# MainBoard.net
KiCad netlist of a schematic drawn in EAGLE
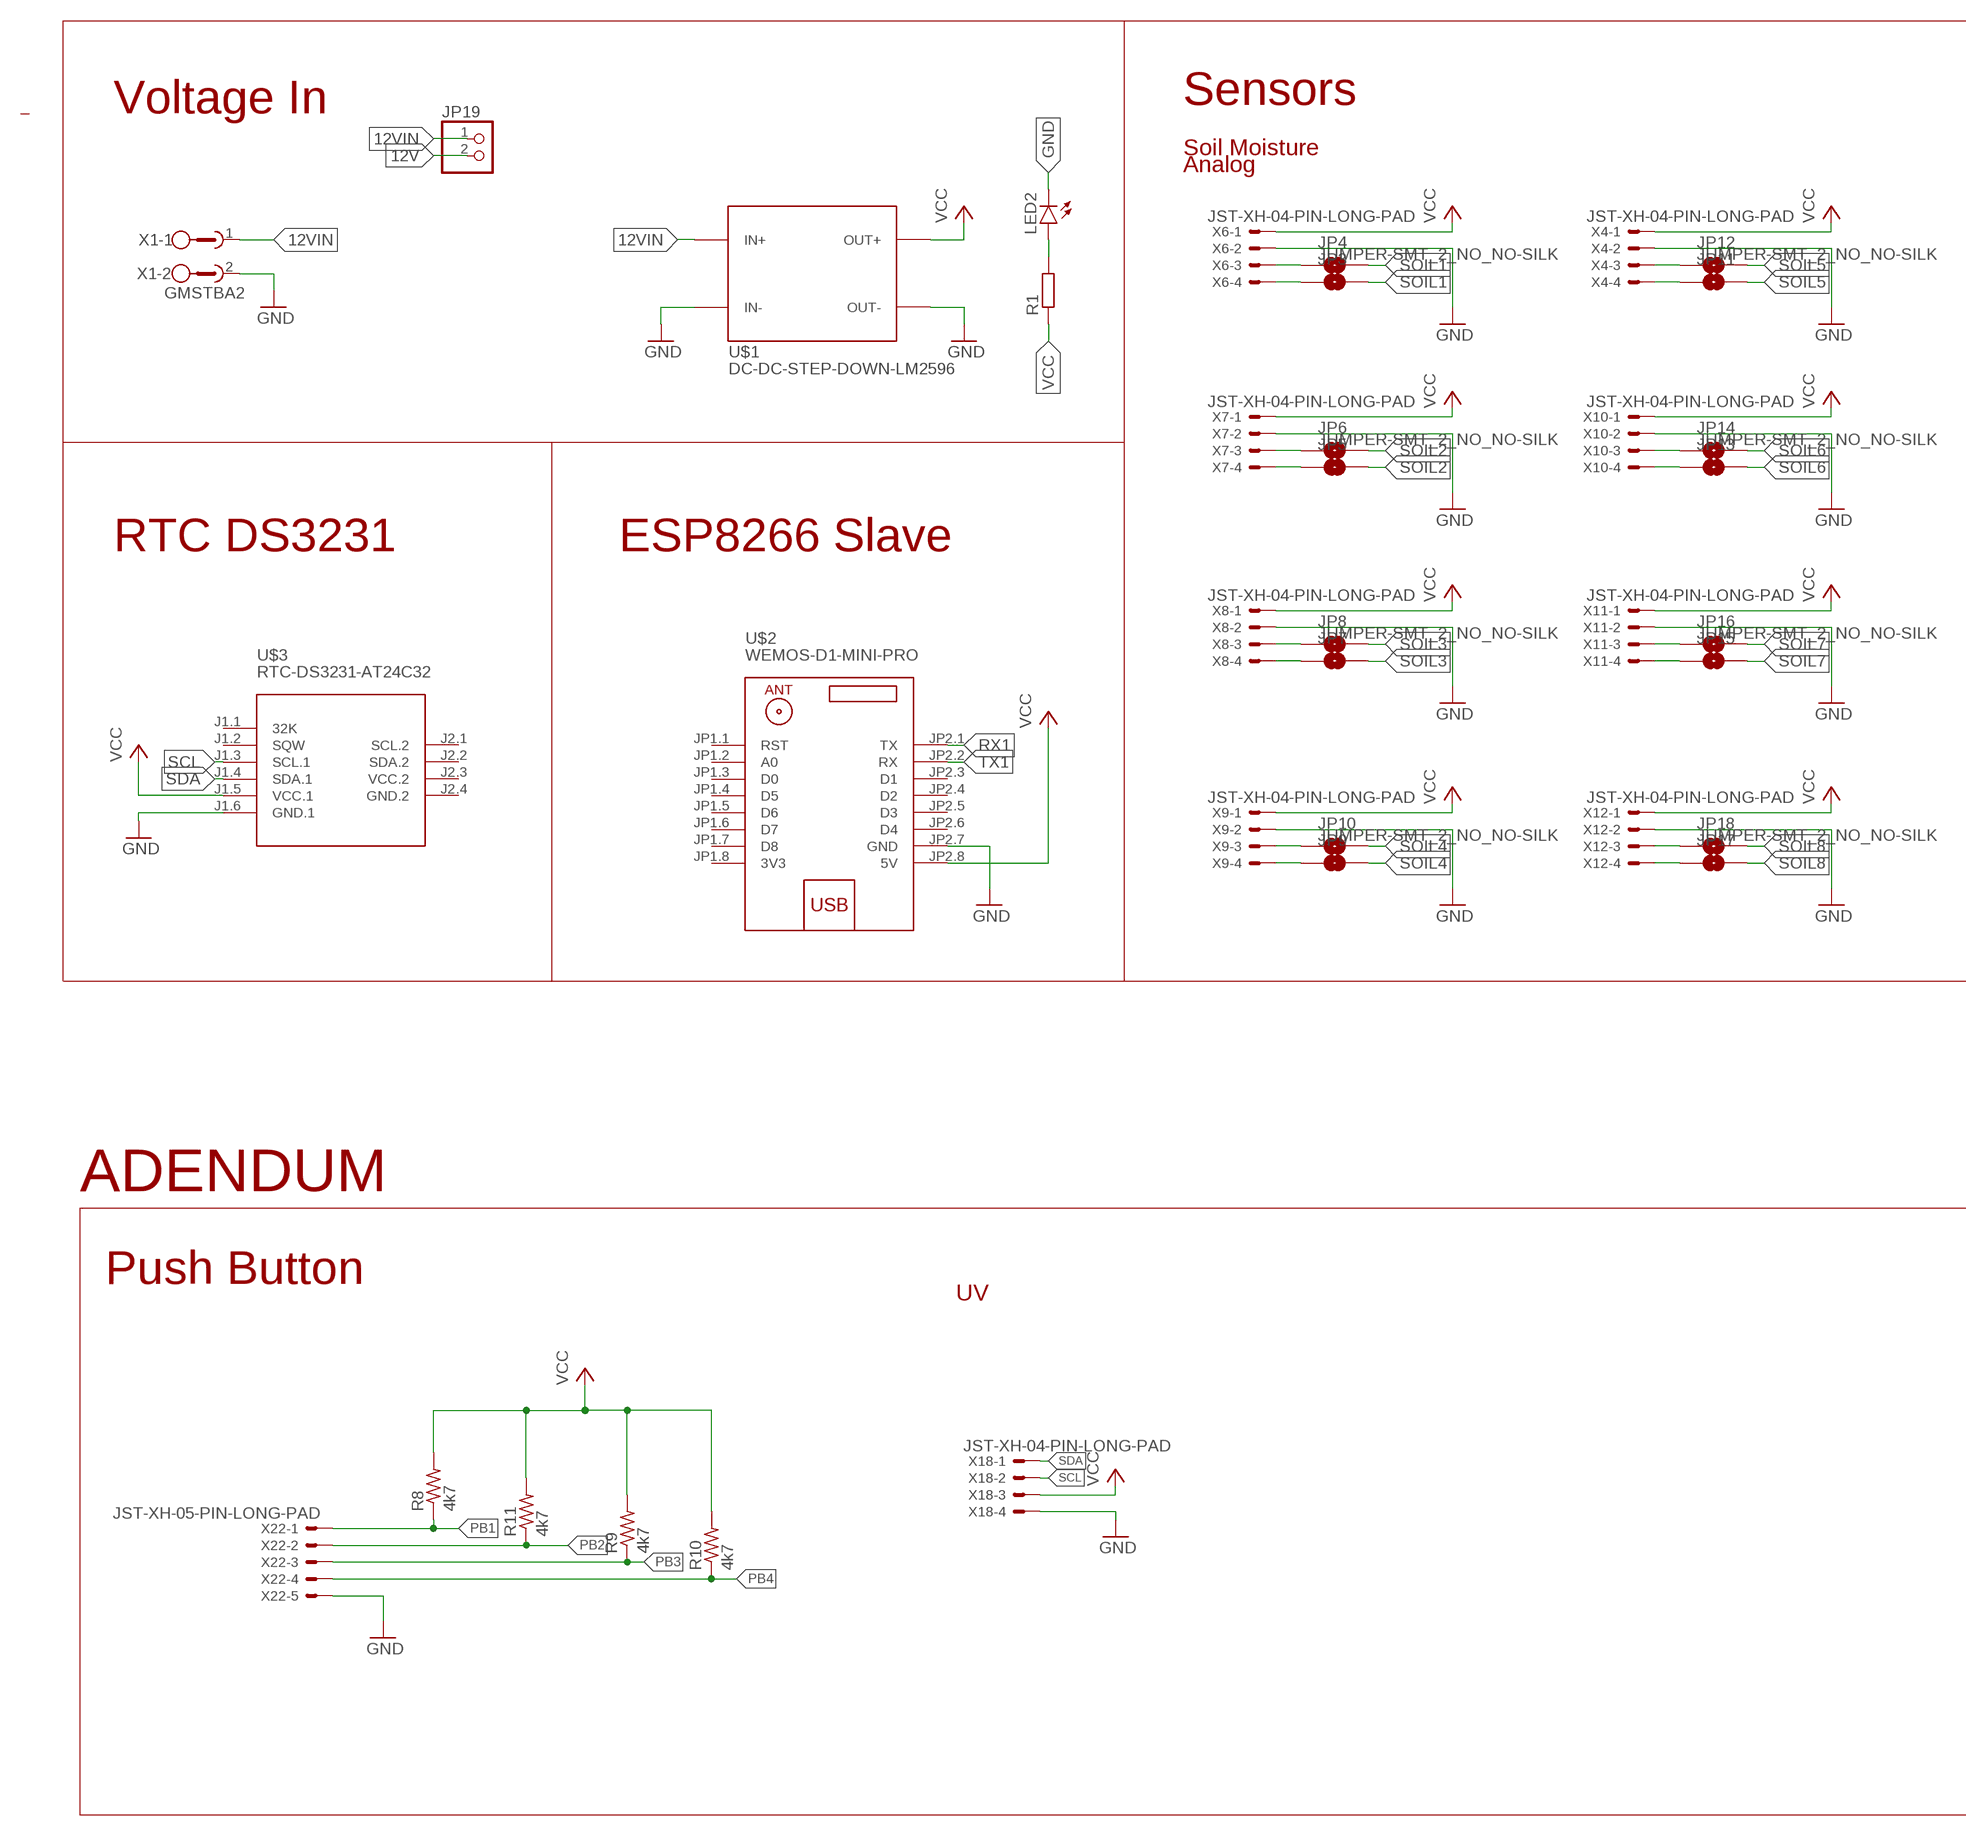
[diagram p0: schematic, sheet 1, part 1 of 2]
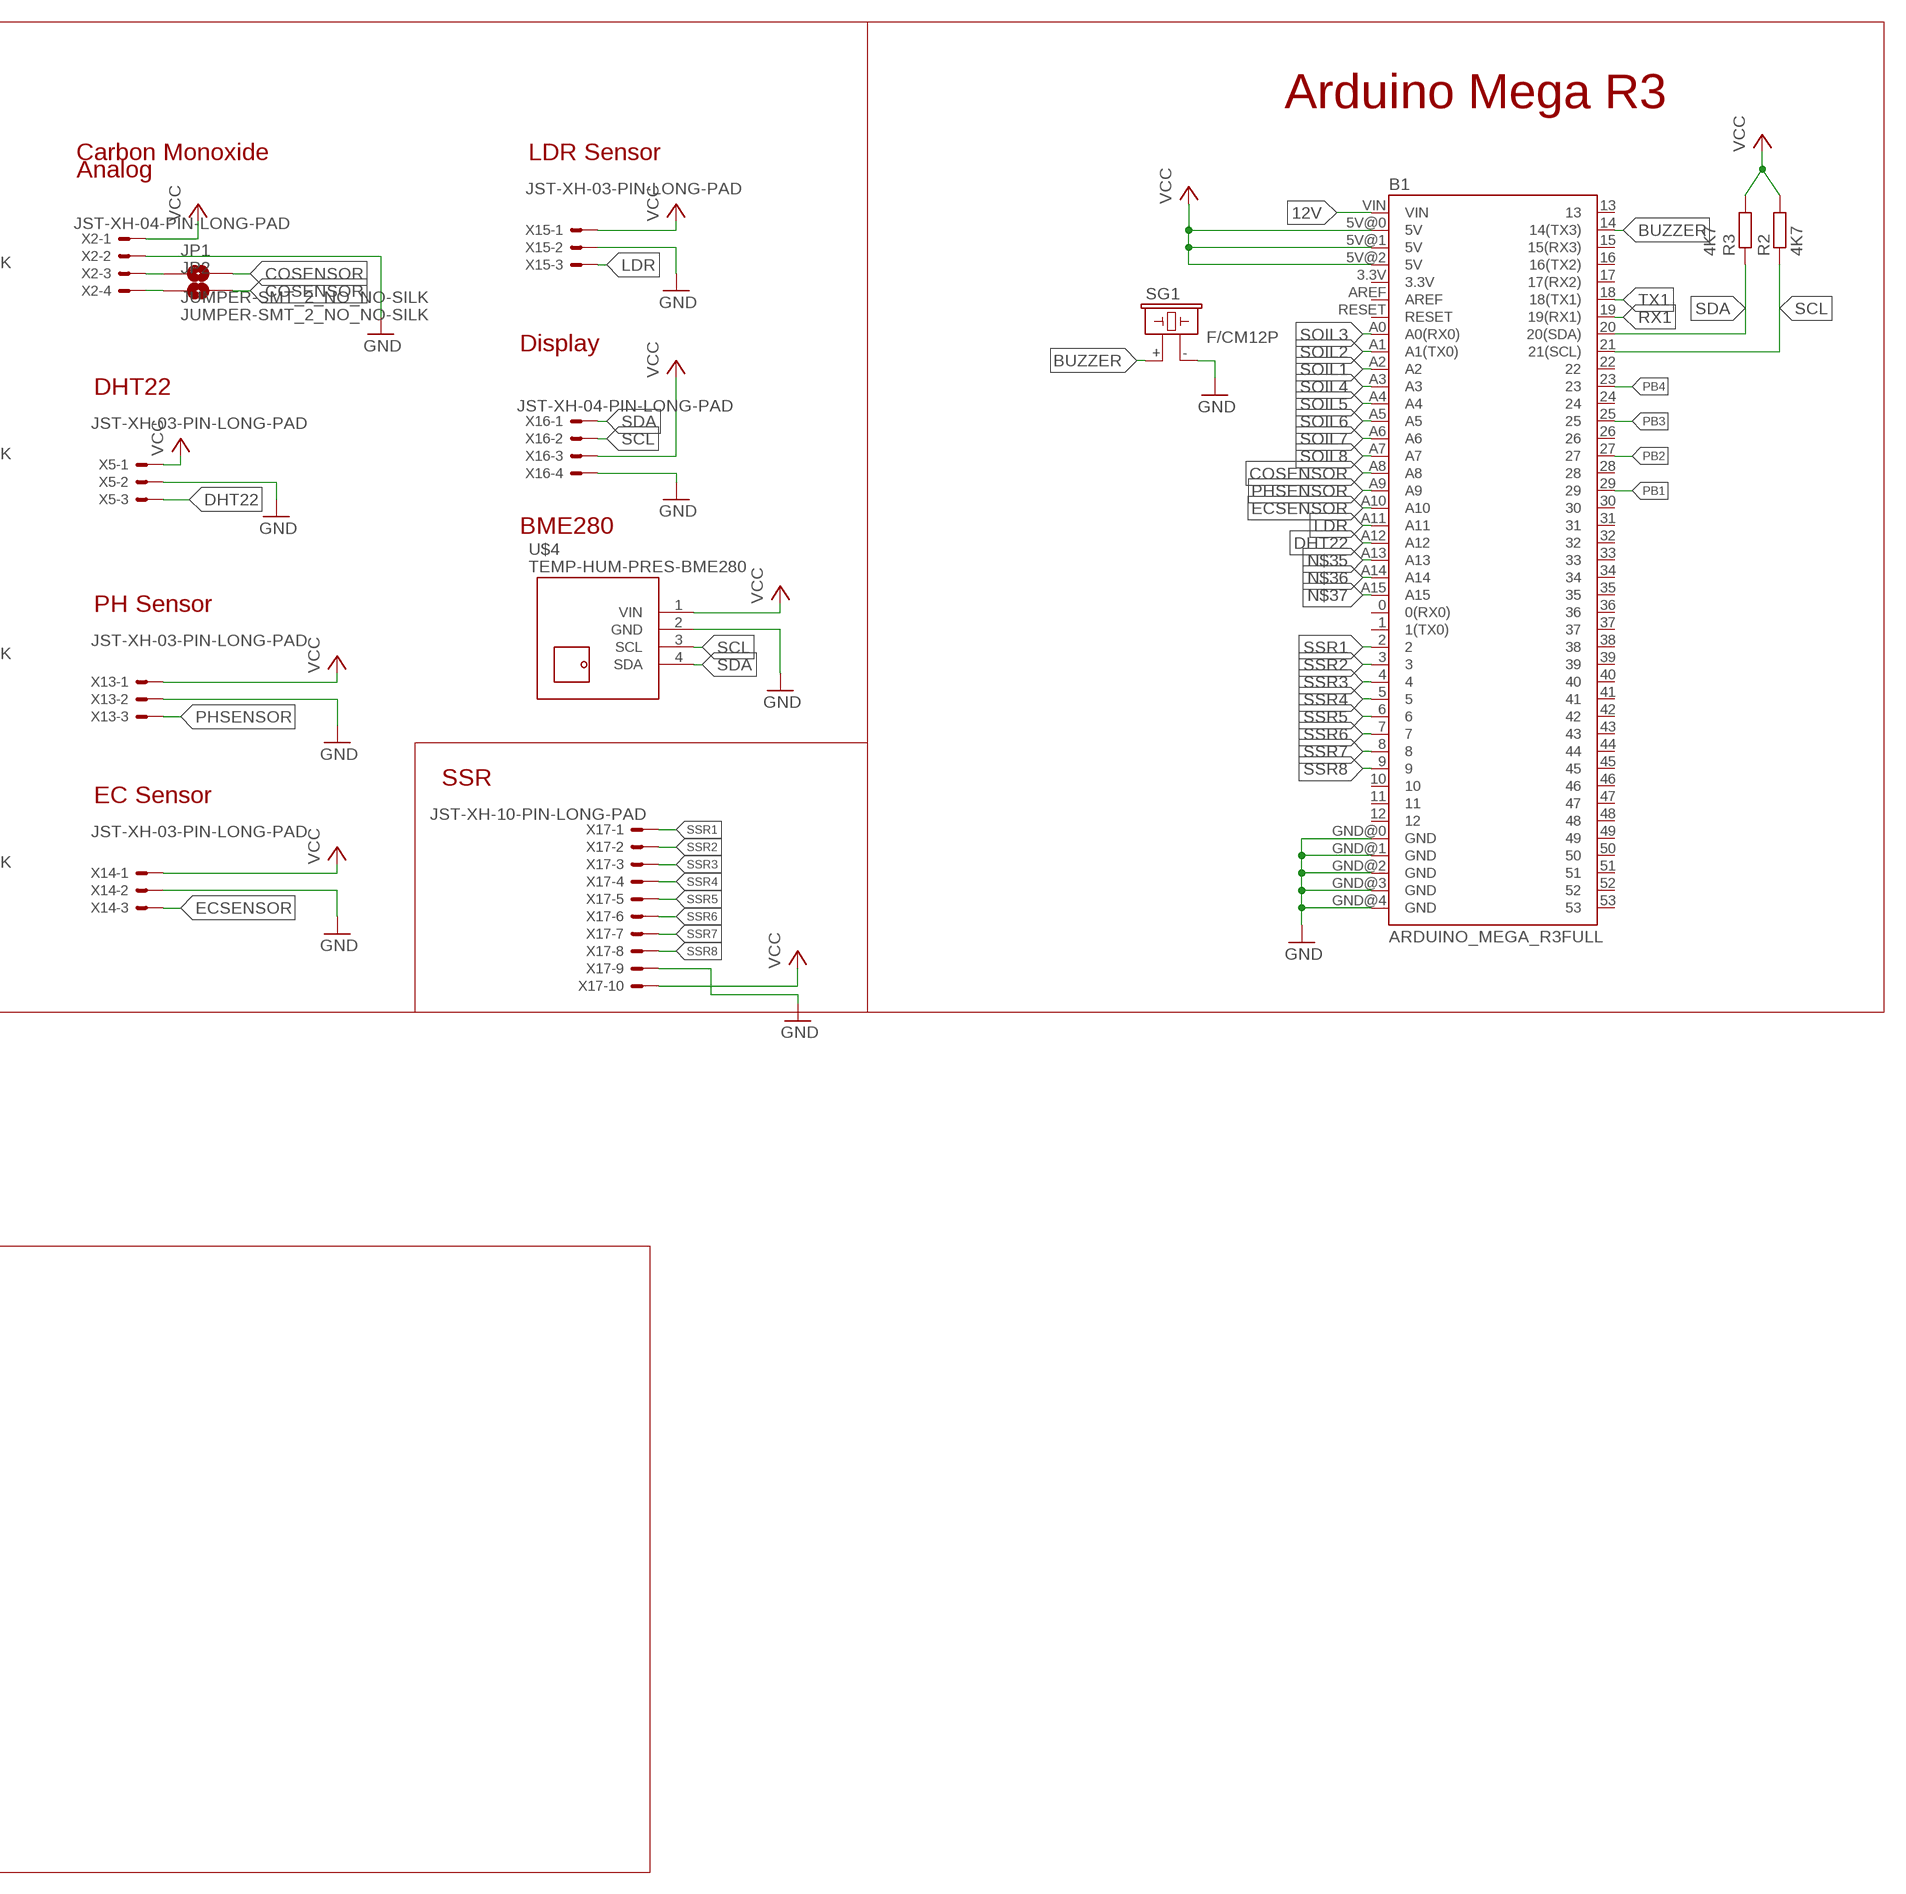
[diagram p1: schematic, sheet 1, part 2 of 2]

(export (version "E")
  (design (tool "Eeschema 10.0.6"))
  (components
    (comp (ref "B1")
      (value "ARDUINO_MEGA_R3FULL")
      (footprint "eagle-import:ARDUINO_MEGA")
      (libsource (lib "eagle-import") (part "ARDUINO_MEGA_R3FULL"))
    )
    (comp (ref "JP1")
      (value "JUMPER-SMT_2_NO_NO-SILK")
      (footprint "eagle-import:SMT-JUMPER_2_NO_NO-SILK")
      (libsource (lib "eagle-import") (part "JUMPER-SMT_2_NO_NO-SILK"))
    )
    (comp (ref "JP2")
      (value "JUMPER-SMT_2_NO_NO-SILK")
      (footprint "eagle-import:SMT-JUMPER_2_NO_NO-SILK")
      (libsource (lib "eagle-import") (part "JUMPER-SMT_2_NO_NO-SILK"))
    )
    (comp (ref "JP3")
      (value "JUMPER-SMT_2_NO_NO-SILK")
      (footprint "eagle-import:SMT-JUMPER_2_NO_NO-SILK")
      (libsource (lib "eagle-import") (part "JUMPER-SMT_2_NO_NO-SILK"))
    )
    (comp (ref "JP4")
      (value "JUMPER-SMT_2_NO_NO-SILK")
      (footprint "eagle-import:SMT-JUMPER_2_NO_NO-SILK")
      (libsource (lib "eagle-import") (part "JUMPER-SMT_2_NO_NO-SILK"))
    )
    (comp (ref "JP5")
      (value "JUMPER-SMT_2_NO_NO-SILK")
      (footprint "eagle-import:SMT-JUMPER_2_NO_NO-SILK")
      (libsource (lib "eagle-import") (part "JUMPER-SMT_2_NO_NO-SILK"))
    )
    (comp (ref "JP6")
      (value "JUMPER-SMT_2_NO_NO-SILK")
      (footprint "eagle-import:SMT-JUMPER_2_NO_NO-SILK")
      (libsource (lib "eagle-import") (part "JUMPER-SMT_2_NO_NO-SILK"))
    )
    (comp (ref "JP7")
      (value "JUMPER-SMT_2_NO_NO-SILK")
      (footprint "eagle-import:SMT-JUMPER_2_NO_NO-SILK")
      (libsource (lib "eagle-import") (part "JUMPER-SMT_2_NO_NO-SILK"))
    )
    (comp (ref "JP8")
      (value "JUMPER-SMT_2_NO_NO-SILK")
      (footprint "eagle-import:SMT-JUMPER_2_NO_NO-SILK")
      (libsource (lib "eagle-import") (part "JUMPER-SMT_2_NO_NO-SILK"))
    )
    (comp (ref "JP9")
      (value "JUMPER-SMT_2_NO_NO-SILK")
      (footprint "eagle-import:SMT-JUMPER_2_NO_NO-SILK")
      (libsource (lib "eagle-import") (part "JUMPER-SMT_2_NO_NO-SILK"))
    )
    (comp (ref "JP10")
      (value "JUMPER-SMT_2_NO_NO-SILK")
      (footprint "eagle-import:SMT-JUMPER_2_NO_NO-SILK")
      (libsource (lib "eagle-import") (part "JUMPER-SMT_2_NO_NO-SILK"))
    )
    (comp (ref "JP11")
      (value "JUMPER-SMT_2_NO_NO-SILK")
      (footprint "eagle-import:SMT-JUMPER_2_NO_NO-SILK")
      (libsource (lib "eagle-import") (part "JUMPER-SMT_2_NO_NO-SILK"))
    )
    (comp (ref "JP12")
      (value "JUMPER-SMT_2_NO_NO-SILK")
      (footprint "eagle-import:SMT-JUMPER_2_NO_NO-SILK")
      (libsource (lib "eagle-import") (part "JUMPER-SMT_2_NO_NO-SILK"))
    )
    (comp (ref "JP13")
      (value "JUMPER-SMT_2_NO_NO-SILK")
      (footprint "eagle-import:SMT-JUMPER_2_NO_NO-SILK")
      (libsource (lib "eagle-import") (part "JUMPER-SMT_2_NO_NO-SILK"))
    )
    (comp (ref "JP14")
      (value "JUMPER-SMT_2_NO_NO-SILK")
      (footprint "eagle-import:SMT-JUMPER_2_NO_NO-SILK")
      (libsource (lib "eagle-import") (part "JUMPER-SMT_2_NO_NO-SILK"))
    )
    (comp (ref "JP15")
      (value "JUMPER-SMT_2_NO_NO-SILK")
      (footprint "eagle-import:SMT-JUMPER_2_NO_NO-SILK")
      (libsource (lib "eagle-import") (part "JUMPER-SMT_2_NO_NO-SILK"))
    )
    (comp (ref "JP16")
      (value "JUMPER-SMT_2_NO_NO-SILK")
      (footprint "eagle-import:SMT-JUMPER_2_NO_NO-SILK")
      (libsource (lib "eagle-import") (part "JUMPER-SMT_2_NO_NO-SILK"))
    )
    (comp (ref "JP17")
      (value "JUMPER-SMT_2_NO_NO-SILK")
      (footprint "eagle-import:SMT-JUMPER_2_NO_NO-SILK")
      (libsource (lib "eagle-import") (part "JUMPER-SMT_2_NO_NO-SILK"))
    )
    (comp (ref "JP18")
      (value "JUMPER-SMT_2_NO_NO-SILK")
      (footprint "eagle-import:SMT-JUMPER_2_NO_NO-SILK")
      (libsource (lib "eagle-import") (part "JUMPER-SMT_2_NO_NO-SILK"))
    )
    (comp (ref "JP19")
      (value "PINHD-1X2")
      (footprint "eagle-import:1X02")
      (libsource (lib "eagle-import") (part "PINHD-1X2"))
    )
    (comp (ref "LED2")
      (value "LED5MM")
      (footprint "eagle-import:LED5MM")
      (libsource (lib "eagle-import") (part "LED5MM"))
    )
    (comp (ref "R1")
      (value "R-EU_R0805")
      (footprint "eagle-import:R0805")
      (libsource (lib "eagle-import") (part "rcl_334_R-EU_R0805"))
    )
    (comp (ref "R2")
      (value "4K7")
      (footprint "eagle-import:M0805")
      (libsource (lib "eagle-import") (part "R-EU_M0805"))
    )
    (comp (ref "R3")
      (value "4K7")
      (footprint "eagle-import:M0805")
      (libsource (lib "eagle-import") (part "R-EU_M0805"))
    )
    (comp (ref "R8")
      (value "4k7")
      (footprint "eagle-import:M0805")
      (libsource (lib "eagle-import") (part "R-US_M0805"))
    )
    (comp (ref "R9")
      (value "4k7")
      (footprint "eagle-import:M0805")
      (libsource (lib "eagle-import") (part "R-US_M0805"))
    )
    (comp (ref "R10")
      (value "4k7")
      (footprint "eagle-import:M0805")
      (libsource (lib "eagle-import") (part "R-US_M0805"))
    )
    (comp (ref "R11")
      (value "4k7")
      (footprint "eagle-import:M0805")
      (libsource (lib "eagle-import") (part "R-US_M0805"))
    )
    (comp (ref "SG1")
      (value "F/CM12P")
      (footprint "eagle-import:F_CM12P")
      (libsource (lib "eagle-import") (part "F/CM12P"))
    )
    (comp (ref "U$1")
      (value "DC-DC-STEP-DOWN-LM2596")
      (footprint "eagle-import:DC-DC-STEP-DOWN-LM2596")
      (libsource (lib "eagle-import") (part "DC-DC-STEP-DOWN-LM2596"))
    )
    (comp (ref "U$2")
      (value "WEMOS-D1-MINI-PRO")
      (footprint "eagle-import:WEMOS-D1-MINI-PRO")
      (libsource (lib "eagle-import") (part "WEMOS-D1-MINI-PRO"))
    )
    (comp (ref "U$3")
      (value "RTC-DS3231-AT24C32")
      (footprint "eagle-import:RTC-DS3231-AT24C32")
      (libsource (lib "eagle-import") (part "RTC-DS3231-AT24C32"))
    )
    (comp (ref "U$4")
      (value "TEMP-HUM-PRES-BME280")
      (footprint "eagle-import:TEMP-HUM-PRES-BME280")
      (libsource (lib "eagle-import") (part "TEMP-HUM-PRES-BME280"))
    )
    (comp (ref "X1")
      (value "GMSTBA2")
      (footprint "eagle-import:GMSTBA2")
      (fields (field (name "MF") "FARNELL") (field (name "MPN") "1757242"))
      (libsource (lib "eagle-import") (part "GMSTBA2"))
    )
    (comp (ref "X2")
      (value "JST-XH-04-PIN-LONG-PAD")
      (footprint "eagle-import:JST-XH-04-PACKAGE-LONG-PAD")
      (libsource (lib "eagle-import") (part "JST-XH-04-PIN-LONG-PAD"))
    )
    (comp (ref "X4")
      (value "JST-XH-04-PIN-LONG-PAD")
      (footprint "eagle-import:JST-XH-04-PACKAGE-LONG-PAD")
      (libsource (lib "eagle-import") (part "JST-XH-04-PIN-LONG-PAD"))
    )
    (comp (ref "X5")
      (value "JST-XH-03-PIN-LONG-PAD")
      (footprint "eagle-import:JST-XH-03-PACKAGE-LONG-PAD")
      (libsource (lib "eagle-import") (part "JST-XH-03-PIN-LONG-PAD"))
    )
    (comp (ref "X6")
      (value "JST-XH-04-PIN-LONG-PAD")
      (footprint "eagle-import:JST-XH-04-PACKAGE-LONG-PAD")
      (libsource (lib "eagle-import") (part "JST-XH-04-PIN-LONG-PAD"))
    )
    (comp (ref "X7")
      (value "JST-XH-04-PIN-LONG-PAD")
      (footprint "eagle-import:JST-XH-04-PACKAGE-LONG-PAD")
      (libsource (lib "eagle-import") (part "JST-XH-04-PIN-LONG-PAD"))
    )
    (comp (ref "X8")
      (value "JST-XH-04-PIN-LONG-PAD")
      (footprint "eagle-import:JST-XH-04-PACKAGE-LONG-PAD")
      (libsource (lib "eagle-import") (part "JST-XH-04-PIN-LONG-PAD"))
    )
    (comp (ref "X9")
      (value "JST-XH-04-PIN-LONG-PAD")
      (footprint "eagle-import:JST-XH-04-PACKAGE-LONG-PAD")
      (libsource (lib "eagle-import") (part "JST-XH-04-PIN-LONG-PAD"))
    )
    (comp (ref "X10")
      (value "JST-XH-04-PIN-LONG-PAD")
      (footprint "eagle-import:JST-XH-04-PACKAGE-LONG-PAD")
      (libsource (lib "eagle-import") (part "JST-XH-04-PIN-LONG-PAD"))
    )
    (comp (ref "X11")
      (value "JST-XH-04-PIN-LONG-PAD")
      (footprint "eagle-import:JST-XH-04-PACKAGE-LONG-PAD")
      (libsource (lib "eagle-import") (part "JST-XH-04-PIN-LONG-PAD"))
    )
    (comp (ref "X12")
      (value "JST-XH-04-PIN-LONG-PAD")
      (footprint "eagle-import:JST-XH-04-PACKAGE-LONG-PAD")
      (libsource (lib "eagle-import") (part "JST-XH-04-PIN-LONG-PAD"))
    )
    (comp (ref "X13")
      (value "JST-XH-03-PIN-LONG-PAD")
      (footprint "eagle-import:JST-XH-03-PACKAGE-LONG-PAD")
      (libsource (lib "eagle-import") (part "JST-XH-03-PIN-LONG-PAD"))
    )
    (comp (ref "X14")
      (value "JST-XH-03-PIN-LONG-PAD")
      (footprint "eagle-import:JST-XH-03-PACKAGE-LONG-PAD")
      (libsource (lib "eagle-import") (part "JST-XH-03-PIN-LONG-PAD"))
    )
    (comp (ref "X15")
      (value "JST-XH-03-PIN-LONG-PAD")
      (footprint "eagle-import:JST-XH-03-PACKAGE-LONG-PAD")
      (libsource (lib "eagle-import") (part "JST-XH-03-PIN-LONG-PAD"))
    )
    (comp (ref "X16")
      (value "JST-XH-04-PIN-LONG-PAD")
      (footprint "eagle-import:JST-XH-04-PACKAGE-LONG-PAD")
      (libsource (lib "eagle-import") (part "JST-XH-04-PIN-LONG-PAD"))
    )
    (comp (ref "X17")
      (value "JST-XH-10-PIN-LONG-PAD")
      (footprint "eagle-import:JST-XH-10-PACKAGE-LONG-PAD")
      (libsource (lib "eagle-import") (part "JST-XH-10-PIN-LONG-PAD"))
    )
    (comp (ref "X18")
      (value "JST-XH-04-PIN-LONG-PAD")
      (footprint "eagle-import:JST-XH-04-PACKAGE-LONG-PAD")
      (libsource (lib "eagle-import") (part "JST-XH-04-PIN-LONG-PAD"))
    )
    (comp (ref "X22")
      (value "JST-XH-05-PIN-LONG-PAD")
      (footprint "eagle-import:JST-XH-05-PACKAGE-LONG-PAD")
      (libsource (lib "eagle-import") (part "JST-XH-05-PIN-LONG-PAD"))
    )
  )
  (nets
    (net (code "1") (name "/3V3") (class "Default")
      (node (ref "U$2") (pin "JP1.8") (pinfunction "3V3_JP1.8") (pintype "power_in"))
    )
    (net (code "2") (name "/GND.2") (class "Default")
      (node (ref "U$3") (pin "J2.4") (pinfunction "GND.2_J2.4") (pintype "power_in"))
    )
    (net (code "3") (name "/VCC.2") (class "Default")
      (node (ref "U$3") (pin "J2.3") (pinfunction "VCC.2_J2.3") (pintype "power_in"))
    )
    (net (code "4") (name "12V") (class "Default")
      (node (ref "B1") (pin "VIN") (pinfunction "VIN_VIN") (pintype "bidirectional"))
      (node (ref "JP19") (pin "2") (pinfunction "2_2") (pintype "passive"))
    )
    (net (code "5") (name "12VIN") (class "Default")
      (node (ref "JP19") (pin "1") (pinfunction "1_1") (pintype "passive"))
      (node (ref "U$1") (pin "IN+") (pinfunction "IN+_IN+") (pintype "bidirectional"))
      (node (ref "X1") (pin "1") (pinfunction "1_1") (pintype "passive"))
    )
    (net (code "6") (name "BUZZER") (class "Default")
      (node (ref "B1") (pin "14") (pinfunction "14(TX3)_14") (pintype "bidirectional"))
      (node (ref "SG1") (pin "+") (pinfunction "1_+") (pintype "passive"))
    )
    (net (code "7") (name "COSENSOR") (class "Default")
      (node (ref "B1") (pin "A8") (pinfunction "A8_A8") (pintype "bidirectional"))
      (node (ref "JP1") (pin "2") (pinfunction "2_2") (pintype "passive"))
      (node (ref "JP2") (pin "2") (pinfunction "2_2") (pintype "passive"))
    )
    (net (code "8") (name "DHT22") (class "Default")
      (node (ref "B1") (pin "A12") (pinfunction "A12_A12") (pintype "bidirectional"))
      (node (ref "X5") (pin "3") (pinfunction "S_3") (pintype "passive"))
    )
    (net (code "9") (name "ECSENSOR") (class "Default")
      (node (ref "B1") (pin "A10") (pinfunction "A10_A10") (pintype "bidirectional"))
      (node (ref "X14") (pin "3") (pinfunction "S_3") (pintype "passive"))
    )
    (net (code "10") (name "GND") (class "Default")
      (node (ref "B1") (pin "GND@0") (pinfunction "GND_GND@0") (pintype "bidirectional"))
      (node (ref "B1") (pin "GND@1") (pinfunction "GND_GND@1") (pintype "bidirectional"))
      (node (ref "B1") (pin "GND@2") (pinfunction "GND_GND@2") (pintype "bidirectional"))
      (node (ref "B1") (pin "GND@3") (pinfunction "GND_GND@3") (pintype "bidirectional"))
      (node (ref "B1") (pin "GND@4") (pinfunction "GND_GND@4") (pintype "bidirectional"))
      (node (ref "LED2") (pin "K") (pinfunction "C_K") (pintype "passive"))
      (node (ref "SG1") (pin "-") (pinfunction "2_-") (pintype "passive"))
      (node (ref "U$1") (pin "IN-") (pinfunction "IN-_IN-") (pintype "bidirectional"))
      (node (ref "U$1") (pin "OUT-") (pinfunction "OUT-_OUT-") (pintype "bidirectional"))
      (node (ref "U$2") (pin "JP2.7") (pinfunction "GND_JP2.7") (pintype "power_in"))
      (node (ref "U$3") (pin "J1.6") (pinfunction "GND.1_J1.6") (pintype "power_in"))
      (node (ref "U$4") (pin "2") (pinfunction "GND_2") (pintype "power_in"))
      (node (ref "X1") (pin "2") (pinfunction "1_2") (pintype "passive"))
      (node (ref "X10") (pin "2") (pinfunction "S_2") (pintype "passive"))
      (node (ref "X11") (pin "2") (pinfunction "S_2") (pintype "passive"))
      (node (ref "X12") (pin "2") (pinfunction "S_2") (pintype "passive"))
      (node (ref "X13") (pin "2") (pinfunction "S_2") (pintype "passive"))
      (node (ref "X14") (pin "2") (pinfunction "S_2") (pintype "passive"))
      (node (ref "X15") (pin "2") (pinfunction "S_2") (pintype "passive"))
      (node (ref "X16") (pin "4") (pinfunction "S_4") (pintype "passive"))
      (node (ref "X17") (pin "9") (pinfunction "S_9") (pintype "passive"))
      (node (ref "X18") (pin "4") (pinfunction "S_4") (pintype "passive"))
      (node (ref "X2") (pin "2") (pinfunction "S_2") (pintype "passive"))
      (node (ref "X22") (pin "5") (pinfunction "S_5") (pintype "passive"))
      (node (ref "X4") (pin "2") (pinfunction "S_2") (pintype "passive"))
      (node (ref "X5") (pin "2") (pinfunction "S_2") (pintype "passive"))
      (node (ref "X6") (pin "2") (pinfunction "S_2") (pintype "passive"))
      (node (ref "X7") (pin "2") (pinfunction "S_2") (pintype "passive"))
      (node (ref "X8") (pin "2") (pinfunction "S_2") (pintype "passive"))
      (node (ref "X9") (pin "2") (pinfunction "S_2") (pintype "passive"))
    )
    (net (code "11") (name "LDR") (class "Default")
      (node (ref "B1") (pin "A11") (pinfunction "A11_A11") (pintype "bidirectional"))
      (node (ref "X15") (pin "3") (pinfunction "S_3") (pintype "passive"))
    )
    (net (code "12") (name "N$35") (class "Default")
      (node (ref "B1") (pin "A13") (pinfunction "A13_A13") (pintype "bidirectional"))
    )
    (net (code "13") (name "N$36") (class "Default")
      (node (ref "B1") (pin "A14") (pinfunction "A14_A14") (pintype "bidirectional"))
    )
    (net (code "14") (name "N$37") (class "Default")
      (node (ref "B1") (pin "A15") (pinfunction "A15_A15") (pintype "bidirectional"))
    )
    (net (code "15") (name "Net-(LED2-PadA)") (class "Default")
      (node (ref "LED2") (pin "A") (pinfunction "A_A") (pintype "passive"))
      (node (ref "R1") (pin "2") (pinfunction "2_2") (pintype "passive"))
    )
    (net (code "16") (name "Net-(X2C-S)") (class "Default")
      (node (ref "JP1") (pin "1") (pinfunction "1_1") (pintype "passive"))
      (node (ref "X2") (pin "3") (pinfunction "S_3") (pintype "passive"))
    )
    (net (code "17") (name "Net-(X2D-S)") (class "Default")
      (node (ref "JP2") (pin "1") (pinfunction "1_1") (pintype "passive"))
      (node (ref "X2") (pin "4") (pinfunction "S_4") (pintype "passive"))
    )
    (net (code "18") (name "Net-(X4C-S)") (class "Default")
      (node (ref "JP12") (pin "1") (pinfunction "1_1") (pintype "passive"))
      (node (ref "X4") (pin "3") (pinfunction "S_3") (pintype "passive"))
    )
    (net (code "19") (name "Net-(X4D-S)") (class "Default")
      (node (ref "JP11") (pin "1") (pinfunction "1_1") (pintype "passive"))
      (node (ref "X4") (pin "4") (pinfunction "S_4") (pintype "passive"))
    )
    (net (code "20") (name "Net-(X6C-S)") (class "Default")
      (node (ref "JP4") (pin "1") (pinfunction "1_1") (pintype "passive"))
      (node (ref "X6") (pin "3") (pinfunction "S_3") (pintype "passive"))
    )
    (net (code "21") (name "Net-(X6D-S)") (class "Default")
      (node (ref "JP3") (pin "1") (pinfunction "1_1") (pintype "passive"))
      (node (ref "X6") (pin "4") (pinfunction "S_4") (pintype "passive"))
    )
    (net (code "22") (name "Net-(X7C-S)") (class "Default")
      (node (ref "JP6") (pin "1") (pinfunction "1_1") (pintype "passive"))
      (node (ref "X7") (pin "3") (pinfunction "S_3") (pintype "passive"))
    )
    (net (code "23") (name "Net-(X7D-S)") (class "Default")
      (node (ref "JP5") (pin "1") (pinfunction "1_1") (pintype "passive"))
      (node (ref "X7") (pin "4") (pinfunction "S_4") (pintype "passive"))
    )
    (net (code "24") (name "Net-(X8C-S)") (class "Default")
      (node (ref "JP8") (pin "1") (pinfunction "1_1") (pintype "passive"))
      (node (ref "X8") (pin "3") (pinfunction "S_3") (pintype "passive"))
    )
    (net (code "25") (name "Net-(X8D-S)") (class "Default")
      (node (ref "JP7") (pin "1") (pinfunction "1_1") (pintype "passive"))
      (node (ref "X8") (pin "4") (pinfunction "S_4") (pintype "passive"))
    )
    (net (code "26") (name "Net-(X9C-S)") (class "Default")
      (node (ref "JP10") (pin "1") (pinfunction "1_1") (pintype "passive"))
      (node (ref "X9") (pin "3") (pinfunction "S_3") (pintype "passive"))
    )
    (net (code "27") (name "Net-(X9D-S)") (class "Default")
      (node (ref "JP9") (pin "1") (pinfunction "1_1") (pintype "passive"))
      (node (ref "X9") (pin "4") (pinfunction "S_4") (pintype "passive"))
    )
    (net (code "28") (name "Net-(X10C-S)") (class "Default")
      (node (ref "JP14") (pin "1") (pinfunction "1_1") (pintype "passive"))
      (node (ref "X10") (pin "3") (pinfunction "S_3") (pintype "passive"))
    )
    (net (code "29") (name "Net-(X10D-S)") (class "Default")
      (node (ref "JP13") (pin "1") (pinfunction "1_1") (pintype "passive"))
      (node (ref "X10") (pin "4") (pinfunction "S_4") (pintype "passive"))
    )
    (net (code "30") (name "Net-(X11C-S)") (class "Default")
      (node (ref "JP16") (pin "1") (pinfunction "1_1") (pintype "passive"))
      (node (ref "X11") (pin "3") (pinfunction "S_3") (pintype "passive"))
    )
    (net (code "31") (name "Net-(X11D-S)") (class "Default")
      (node (ref "JP15") (pin "1") (pinfunction "1_1") (pintype "passive"))
      (node (ref "X11") (pin "4") (pinfunction "S_4") (pintype "passive"))
    )
    (net (code "32") (name "Net-(X12C-S)") (class "Default")
      (node (ref "JP18") (pin "1") (pinfunction "1_1") (pintype "passive"))
      (node (ref "X12") (pin "3") (pinfunction "S_3") (pintype "passive"))
    )
    (net (code "33") (name "Net-(X12D-S)") (class "Default")
      (node (ref "JP17") (pin "1") (pinfunction "1_1") (pintype "passive"))
      (node (ref "X12") (pin "4") (pinfunction "S_4") (pintype "passive"))
    )
    (net (code "34") (name "PB1") (class "Default")
      (node (ref "B1") (pin "29") (pinfunction "29_29") (pintype "bidirectional"))
      (node (ref "R8") (pin "1") (pinfunction "1_1") (pintype "passive"))
      (node (ref "X22") (pin "1") (pinfunction "S_1") (pintype "passive"))
    )
    (net (code "35") (name "PB2") (class "Default")
      (node (ref "B1") (pin "27") (pinfunction "27_27") (pintype "bidirectional"))
      (node (ref "R11") (pin "1") (pinfunction "1_1") (pintype "passive"))
      (node (ref "X22") (pin "2") (pinfunction "S_2") (pintype "passive"))
    )
    (net (code "36") (name "PB3") (class "Default")
      (node (ref "B1") (pin "25") (pinfunction "25_25") (pintype "bidirectional"))
      (node (ref "R9") (pin "1") (pinfunction "1_1") (pintype "passive"))
      (node (ref "X22") (pin "3") (pinfunction "S_3") (pintype "passive"))
    )
    (net (code "37") (name "PB4") (class "Default")
      (node (ref "B1") (pin "23") (pinfunction "23_23") (pintype "bidirectional"))
      (node (ref "R10") (pin "1") (pinfunction "1_1") (pintype "passive"))
      (node (ref "X22") (pin "4") (pinfunction "S_4") (pintype "passive"))
    )
    (net (code "38") (name "PHSENSOR") (class "Default")
      (node (ref "B1") (pin "A9") (pinfunction "A9_A9") (pintype "bidirectional"))
      (node (ref "X13") (pin "3") (pinfunction "S_3") (pintype "passive"))
    )
    (net (code "39") (name "RX1") (class "Default")
      (node (ref "B1") (pin "19") (pinfunction "19(RX1)_19") (pintype "bidirectional"))
      (node (ref "U$2") (pin "JP2.1") (pinfunction "TX_JP2.1") (pintype "bidirectional"))
    )
    (net (code "40") (name "SCL") (class "Default")
      (node (ref "B1") (pin "21") (pinfunction "21(SCL)_21") (pintype "bidirectional"))
      (node (ref "R2") (pin "1") (pinfunction "1_1") (pintype "passive"))
      (node (ref "U$3") (pin "J1.3") (pinfunction "SCL.1_J1.3") (pintype "bidirectional"))
      (node (ref "U$4") (pin "3") (pinfunction "SCL_3") (pintype "bidirectional"))
      (node (ref "X16") (pin "2") (pinfunction "S_2") (pintype "passive"))
      (node (ref "X18") (pin "2") (pinfunction "S_2") (pintype "passive"))
    )
    (net (code "41") (name "SDA") (class "Default")
      (node (ref "B1") (pin "20") (pinfunction "20(SDA)_20") (pintype "bidirectional"))
      (node (ref "R3") (pin "1") (pinfunction "1_1") (pintype "passive"))
      (node (ref "U$3") (pin "J1.4") (pinfunction "SDA.1_J1.4") (pintype "bidirectional"))
      (node (ref "U$4") (pin "4") (pinfunction "SDA_4") (pintype "bidirectional"))
      (node (ref "X16") (pin "1") (pinfunction "S_1") (pintype "passive"))
      (node (ref "X18") (pin "1") (pinfunction "S_1") (pintype "passive"))
    )
    (net (code "42") (name "SOIL1") (class "Default")
      (node (ref "B1") (pin "A2") (pinfunction "A2_A2") (pintype "bidirectional"))
      (node (ref "JP3") (pin "2") (pinfunction "2_2") (pintype "passive"))
      (node (ref "JP4") (pin "2") (pinfunction "2_2") (pintype "passive"))
    )
    (net (code "43") (name "SOIL2") (class "Default")
      (node (ref "B1") (pin "A1") (pinfunction "A1(TX0)_A1") (pintype "bidirectional"))
      (node (ref "JP5") (pin "2") (pinfunction "2_2") (pintype "passive"))
      (node (ref "JP6") (pin "2") (pinfunction "2_2") (pintype "passive"))
    )
    (net (code "44") (name "SOIL3") (class "Default")
      (node (ref "B1") (pin "A0") (pinfunction "A0(RX0)_A0") (pintype "bidirectional"))
      (node (ref "JP7") (pin "2") (pinfunction "2_2") (pintype "passive"))
      (node (ref "JP8") (pin "2") (pinfunction "2_2") (pintype "passive"))
    )
    (net (code "45") (name "SOIL4") (class "Default")
      (node (ref "B1") (pin "A3") (pinfunction "A3_A3") (pintype "bidirectional"))
      (node (ref "JP10") (pin "2") (pinfunction "2_2") (pintype "passive"))
      (node (ref "JP9") (pin "2") (pinfunction "2_2") (pintype "passive"))
    )
    (net (code "46") (name "SOIL5") (class "Default")
      (node (ref "B1") (pin "A4") (pinfunction "A4_A4") (pintype "bidirectional"))
      (node (ref "JP11") (pin "2") (pinfunction "2_2") (pintype "passive"))
      (node (ref "JP12") (pin "2") (pinfunction "2_2") (pintype "passive"))
    )
    (net (code "47") (name "SOIL6") (class "Default")
      (node (ref "B1") (pin "A5") (pinfunction "A5_A5") (pintype "bidirectional"))
      (node (ref "JP13") (pin "2") (pinfunction "2_2") (pintype "passive"))
      (node (ref "JP14") (pin "2") (pinfunction "2_2") (pintype "passive"))
    )
    (net (code "48") (name "SOIL7") (class "Default")
      (node (ref "B1") (pin "A6") (pinfunction "A6_A6") (pintype "bidirectional"))
      (node (ref "JP15") (pin "2") (pinfunction "2_2") (pintype "passive"))
      (node (ref "JP16") (pin "2") (pinfunction "2_2") (pintype "passive"))
    )
    (net (code "49") (name "SOIL8") (class "Default")
      (node (ref "B1") (pin "A7") (pinfunction "A7_A7") (pintype "bidirectional"))
      (node (ref "JP17") (pin "2") (pinfunction "2_2") (pintype "passive"))
      (node (ref "JP18") (pin "2") (pinfunction "2_2") (pintype "passive"))
    )
    (net (code "50") (name "SSR1") (class "Default")
      (node (ref "B1") (pin "2") (pinfunction "2_2") (pintype "bidirectional"))
      (node (ref "X17") (pin "1") (pinfunction "S_1") (pintype "passive"))
    )
    (net (code "51") (name "SSR2") (class "Default")
      (node (ref "B1") (pin "3") (pinfunction "3_3") (pintype "bidirectional"))
      (node (ref "X17") (pin "2") (pinfunction "S_2") (pintype "passive"))
    )
    (net (code "52") (name "SSR3") (class "Default")
      (node (ref "B1") (pin "4") (pinfunction "4_4") (pintype "bidirectional"))
      (node (ref "X17") (pin "3") (pinfunction "S_3") (pintype "passive"))
    )
    (net (code "53") (name "SSR4") (class "Default")
      (node (ref "B1") (pin "5") (pinfunction "5_5") (pintype "bidirectional"))
      (node (ref "X17") (pin "4") (pinfunction "S_4") (pintype "passive"))
    )
    (net (code "54") (name "SSR5") (class "Default")
      (node (ref "B1") (pin "6") (pinfunction "6_6") (pintype "bidirectional"))
      (node (ref "X17") (pin "5") (pinfunction "S_5") (pintype "passive"))
    )
    (net (code "55") (name "SSR6") (class "Default")
      (node (ref "B1") (pin "7") (pinfunction "7_7") (pintype "bidirectional"))
      (node (ref "X17") (pin "6") (pinfunction "S_6") (pintype "passive"))
    )
    (net (code "56") (name "SSR7") (class "Default")
      (node (ref "B1") (pin "8") (pinfunction "8_8") (pintype "bidirectional"))
      (node (ref "X17") (pin "7") (pinfunction "S_7") (pintype "passive"))
    )
    (net (code "57") (name "SSR8") (class "Default")
      (node (ref "B1") (pin "9") (pinfunction "9_9") (pintype "bidirectional"))
      (node (ref "X17") (pin "8") (pinfunction "S_8") (pintype "passive"))
    )
    (net (code "58") (name "TX1") (class "Default")
      (node (ref "B1") (pin "18") (pinfunction "18(TX1)_18") (pintype "bidirectional"))
      (node (ref "U$2") (pin "JP2.2") (pinfunction "RX_JP2.2") (pintype "bidirectional"))
    )
    (net (code "59") (name "VCC") (class "Default")
      (node (ref "B1") (pin "5V@0") (pinfunction "5V_5V@0") (pintype "bidirectional"))
      (node (ref "B1") (pin "5V@1") (pinfunction "5V_5V@1") (pintype "bidirectional"))
      (node (ref "B1") (pin "5V@2") (pinfunction "5V_5V@2") (pintype "bidirectional"))
      (node (ref "R1") (pin "1") (pinfunction "1_1") (pintype "passive"))
      (node (ref "R10") (pin "2") (pinfunction "2_2") (pintype "passive"))
      (node (ref "R11") (pin "2") (pinfunction "2_2") (pintype "passive"))
      (node (ref "R2") (pin "2") (pinfunction "2_2") (pintype "passive"))
      (node (ref "R3") (pin "2") (pinfunction "2_2") (pintype "passive"))
      (node (ref "R8") (pin "2") (pinfunction "2_2") (pintype "passive"))
      (node (ref "R9") (pin "2") (pinfunction "2_2") (pintype "passive"))
      (node (ref "U$1") (pin "OUT+") (pinfunction "OUT+_OUT+") (pintype "bidirectional"))
      (node (ref "U$2") (pin "JP2.8") (pinfunction "5V_JP2.8") (pintype "power_in"))
      (node (ref "U$3") (pin "J1.5") (pinfunction "VCC.1_J1.5") (pintype "power_in"))
      (node (ref "U$4") (pin "1") (pinfunction "VIN_1") (pintype "power_in"))
      (node (ref "X10") (pin "1") (pinfunction "S_1") (pintype "passive"))
      (node (ref "X11") (pin "1") (pinfunction "S_1") (pintype "passive"))
      (node (ref "X12") (pin "1") (pinfunction "S_1") (pintype "passive"))
      (node (ref "X13") (pin "1") (pinfunction "S_1") (pintype "passive"))
      (node (ref "X14") (pin "1") (pinfunction "S_1") (pintype "passive"))
      (node (ref "X15") (pin "1") (pinfunction "S_1") (pintype "passive"))
      (node (ref "X16") (pin "3") (pinfunction "S_3") (pintype "passive"))
      (node (ref "X17") (pin "10") (pinfunction "S_10") (pintype "passive"))
      (node (ref "X18") (pin "3") (pinfunction "S_3") (pintype "passive"))
      (node (ref "X2") (pin "1") (pinfunction "S_1") (pintype "passive"))
      (node (ref "X4") (pin "1") (pinfunction "S_1") (pintype "passive"))
      (node (ref "X5") (pin "1") (pinfunction "S_1") (pintype "passive"))
      (node (ref "X6") (pin "1") (pinfunction "S_1") (pintype "passive"))
      (node (ref "X7") (pin "1") (pinfunction "S_1") (pintype "passive"))
      (node (ref "X8") (pin "1") (pinfunction "S_1") (pintype "passive"))
      (node (ref "X9") (pin "1") (pinfunction "S_1") (pintype "passive"))
    )
    (net (code "60") (name "unconnected-(B1-0(RX0)-Pad0)") (class "Default")
      (node (ref "B1") (pin "0") (pinfunction "0(RX0)_0") (pintype "bidirectional"))
    )
    (net (code "61") (name "unconnected-(B1-1(TX0)-Pad1)") (class "Default")
      (node (ref "B1") (pin "1") (pinfunction "1(TX0)_1") (pintype "bidirectional"))
    )
    (net (code "62") (name "unconnected-(B1-15(RX3)-Pad15)") (class "Default")
      (node (ref "B1") (pin "15") (pinfunction "15(RX3)_15") (pintype "bidirectional"))
    )
    (net (code "63") (name "unconnected-(B1-16(TX2)-Pad16)") (class "Default")
      (node (ref "B1") (pin "16") (pinfunction "16(TX2)_16") (pintype "bidirectional"))
    )
    (net (code "64") (name "unconnected-(B1-17(RX2)-Pad17)") (class "Default")
      (node (ref "B1") (pin "17") (pinfunction "17(RX2)_17") (pintype "bidirectional"))
    )
    (net (code "65") (name "unconnected-(B1-Pad3.3V)") (class "Default")
      (node (ref "B1") (pin "3.3V") (pinfunction "3.3V_3.3V") (pintype "bidirectional"))
    )
    (net (code "66") (name "unconnected-(B1-Pad10)") (class "Default")
      (node (ref "B1") (pin "10") (pinfunction "10_10") (pintype "bidirectional"))
    )
    (net (code "67") (name "unconnected-(B1-Pad11)") (class "Default")
      (node (ref "B1") (pin "11") (pinfunction "11_11") (pintype "bidirectional"))
    )
    (net (code "68") (name "unconnected-(B1-Pad12)") (class "Default")
      (node (ref "B1") (pin "12") (pinfunction "12_12") (pintype "bidirectional"))
    )
    (net (code "69") (name "unconnected-(B1-Pad13)") (class "Default")
      (node (ref "B1") (pin "13") (pinfunction "13_13") (pintype "bidirectional"))
    )
    (net (code "70") (name "unconnected-(B1-Pad22)") (class "Default")
      (node (ref "B1") (pin "22") (pinfunction "22_22") (pintype "bidirectional"))
    )
    (net (code "71") (name "unconnected-(B1-Pad24)") (class "Default")
      (node (ref "B1") (pin "24") (pinfunction "24_24") (pintype "bidirectional"))
    )
    (net (code "72") (name "unconnected-(B1-Pad26)") (class "Default")
      (node (ref "B1") (pin "26") (pinfunction "26_26") (pintype "bidirectional"))
    )
    (net (code "73") (name "unconnected-(B1-Pad28)") (class "Default")
      (node (ref "B1") (pin "28") (pinfunction "28_28") (pintype "bidirectional"))
    )
    (net (code "74") (name "unconnected-(B1-Pad30)") (class "Default")
      (node (ref "B1") (pin "30") (pinfunction "30_30") (pintype "bidirectional"))
    )
    (net (code "75") (name "unconnected-(B1-Pad31)") (class "Default")
      (node (ref "B1") (pin "31") (pinfunction "31_31") (pintype "bidirectional"))
    )
    (net (code "76") (name "unconnected-(B1-Pad32)") (class "Default")
      (node (ref "B1") (pin "32") (pinfunction "32_32") (pintype "bidirectional"))
    )
    (net (code "77") (name "unconnected-(B1-Pad33)") (class "Default")
      (node (ref "B1") (pin "33") (pinfunction "33_33") (pintype "bidirectional"))
    )
    (net (code "78") (name "unconnected-(B1-Pad34)") (class "Default")
      (node (ref "B1") (pin "34") (pinfunction "34_34") (pintype "bidirectional"))
    )
    (net (code "79") (name "unconnected-(B1-Pad35)") (class "Default")
      (node (ref "B1") (pin "35") (pinfunction "35_35") (pintype "bidirectional"))
    )
    (net (code "80") (name "unconnected-(B1-Pad36)") (class "Default")
      (node (ref "B1") (pin "36") (pinfunction "36_36") (pintype "bidirectional"))
    )
    (net (code "81") (name "unconnected-(B1-Pad37)") (class "Default")
      (node (ref "B1") (pin "37") (pinfunction "37_37") (pintype "bidirectional"))
    )
    (net (code "82") (name "unconnected-(B1-Pad38)") (class "Default")
      (node (ref "B1") (pin "38") (pinfunction "38_38") (pintype "bidirectional"))
    )
    (net (code "83") (name "unconnected-(B1-Pad39)") (class "Default")
      (node (ref "B1") (pin "39") (pinfunction "39_39") (pintype "bidirectional"))
    )
    (net (code "84") (name "unconnected-(B1-Pad40)") (class "Default")
      (node (ref "B1") (pin "40") (pinfunction "40_40") (pintype "bidirectional"))
    )
    (net (code "85") (name "unconnected-(B1-Pad41)") (class "Default")
      (node (ref "B1") (pin "41") (pinfunction "41_41") (pintype "bidirectional"))
    )
    (net (code "86") (name "unconnected-(B1-Pad42)") (class "Default")
      (node (ref "B1") (pin "42") (pinfunction "42_42") (pintype "bidirectional"))
    )
    (net (code "87") (name "unconnected-(B1-Pad43)") (class "Default")
      (node (ref "B1") (pin "43") (pinfunction "43_43") (pintype "bidirectional"))
    )
    (net (code "88") (name "unconnected-(B1-Pad44)") (class "Default")
      (node (ref "B1") (pin "44") (pinfunction "44_44") (pintype "bidirectional"))
    )
    (net (code "89") (name "unconnected-(B1-Pad45)") (class "Default")
      (node (ref "B1") (pin "45") (pinfunction "45_45") (pintype "bidirectional"))
    )
    (net (code "90") (name "unconnected-(B1-Pad46)") (class "Default")
      (node (ref "B1") (pin "46") (pinfunction "46_46") (pintype "bidirectional"))
    )
    (net (code "91") (name "unconnected-(B1-Pad47)") (class "Default")
      (node (ref "B1") (pin "47") (pinfunction "47_47") (pintype "bidirectional"))
    )
    (net (code "92") (name "unconnected-(B1-Pad48)") (class "Default")
      (node (ref "B1") (pin "48") (pinfunction "48_48") (pintype "bidirectional"))
    )
    (net (code "93") (name "unconnected-(B1-Pad49)") (class "Default")
      (node (ref "B1") (pin "49") (pinfunction "49_49") (pintype "bidirectional"))
    )
    (net (code "94") (name "unconnected-(B1-Pad50)") (class "Default")
      (node (ref "B1") (pin "50") (pinfunction "50_50") (pintype "bidirectional"))
    )
    (net (code "95") (name "unconnected-(B1-Pad51)") (class "Default")
      (node (ref "B1") (pin "51") (pinfunction "51_51") (pintype "bidirectional"))
    )
    (net (code "96") (name "unconnected-(B1-Pad52)") (class "Default")
      (node (ref "B1") (pin "52") (pinfunction "52_52") (pintype "bidirectional"))
    )
    (net (code "97") (name "unconnected-(B1-Pad53)") (class "Default")
      (node (ref "B1") (pin "53") (pinfunction "53_53") (pintype "bidirectional"))
    )
    (net (code "98") (name "unconnected-(B1-PadAREF)") (class "Default")
      (node (ref "B1") (pin "AREF") (pinfunction "AREF_AREF") (pintype "bidirectional"))
    )
    (net (code "99") (name "unconnected-(B1-PadRESET)") (class "Default")
      (node (ref "B1") (pin "RESET") (pinfunction "RESET_RESET") (pintype "bidirectional"))
    )
    (net (code "100") (name "unconnected-(U$2-A0-PadJP1.2)") (class "Default")
      (node (ref "U$2") (pin "JP1.2") (pinfunction "A0_JP1.2") (pintype "bidirectional"))
    )
    (net (code "101") (name "unconnected-(U$2-D0-PadJP1.3)") (class "Default")
      (node (ref "U$2") (pin "JP1.3") (pinfunction "D0_JP1.3") (pintype "bidirectional"))
    )
    (net (code "102") (name "unconnected-(U$2-D1-PadJP2.3)") (class "Default")
      (node (ref "U$2") (pin "JP2.3") (pinfunction "D1_JP2.3") (pintype "bidirectional"))
    )
    (net (code "103") (name "unconnected-(U$2-D2-PadJP2.4)") (class "Default")
      (node (ref "U$2") (pin "JP2.4") (pinfunction "D2_JP2.4") (pintype "bidirectional"))
    )
    (net (code "104") (name "unconnected-(U$2-D3-PadJP2.5)") (class "Default")
      (node (ref "U$2") (pin "JP2.5") (pinfunction "D3_JP2.5") (pintype "bidirectional"))
    )
    (net (code "105") (name "unconnected-(U$2-D4-PadJP2.6)") (class "Default")
      (node (ref "U$2") (pin "JP2.6") (pinfunction "D4_JP2.6") (pintype "bidirectional"))
    )
    (net (code "106") (name "unconnected-(U$2-D5-PadJP1.4)") (class "Default")
      (node (ref "U$2") (pin "JP1.4") (pinfunction "D5_JP1.4") (pintype "bidirectional"))
    )
    (net (code "107") (name "unconnected-(U$2-D6-PadJP1.5)") (class "Default")
      (node (ref "U$2") (pin "JP1.5") (pinfunction "D6_JP1.5") (pintype "bidirectional"))
    )
    (net (code "108") (name "unconnected-(U$2-D7-PadJP1.6)") (class "Default")
      (node (ref "U$2") (pin "JP1.6") (pinfunction "D7_JP1.6") (pintype "bidirectional"))
    )
    (net (code "109") (name "unconnected-(U$2-D8-PadJP1.7)") (class "Default")
      (node (ref "U$2") (pin "JP1.7") (pinfunction "D8_JP1.7") (pintype "bidirectional"))
    )
    (net (code "110") (name "unconnected-(U$2-RST-PadJP1.1)") (class "Default")
      (node (ref "U$2") (pin "JP1.1") (pinfunction "RST_JP1.1") (pintype "bidirectional"))
    )
    (net (code "111") (name "unconnected-(U$3-32K-PadJ1.1)") (class "Default")
      (node (ref "U$3") (pin "J1.1") (pinfunction "32K_J1.1") (pintype "bidirectional"))
    )
    (net (code "112") (name "unconnected-(U$3-SCL.2-PadJ2.1)") (class "Default")
      (node (ref "U$3") (pin "J2.1") (pinfunction "SCL.2_J2.1") (pintype "bidirectional"))
    )
    (net (code "113") (name "unconnected-(U$3-SDA.2-PadJ2.2)") (class "Default")
      (node (ref "U$3") (pin "J2.2") (pinfunction "SDA.2_J2.2") (pintype "bidirectional"))
    )
    (net (code "114") (name "unconnected-(U$3-SQW-PadJ1.2)") (class "Default")
      (node (ref "U$3") (pin "J1.2") (pinfunction "SQW_J1.2") (pintype "bidirectional"))
    )
  )
)
